# BTP_gateway_board.net
KiCad netlist of a schematic drawn in EAGLE
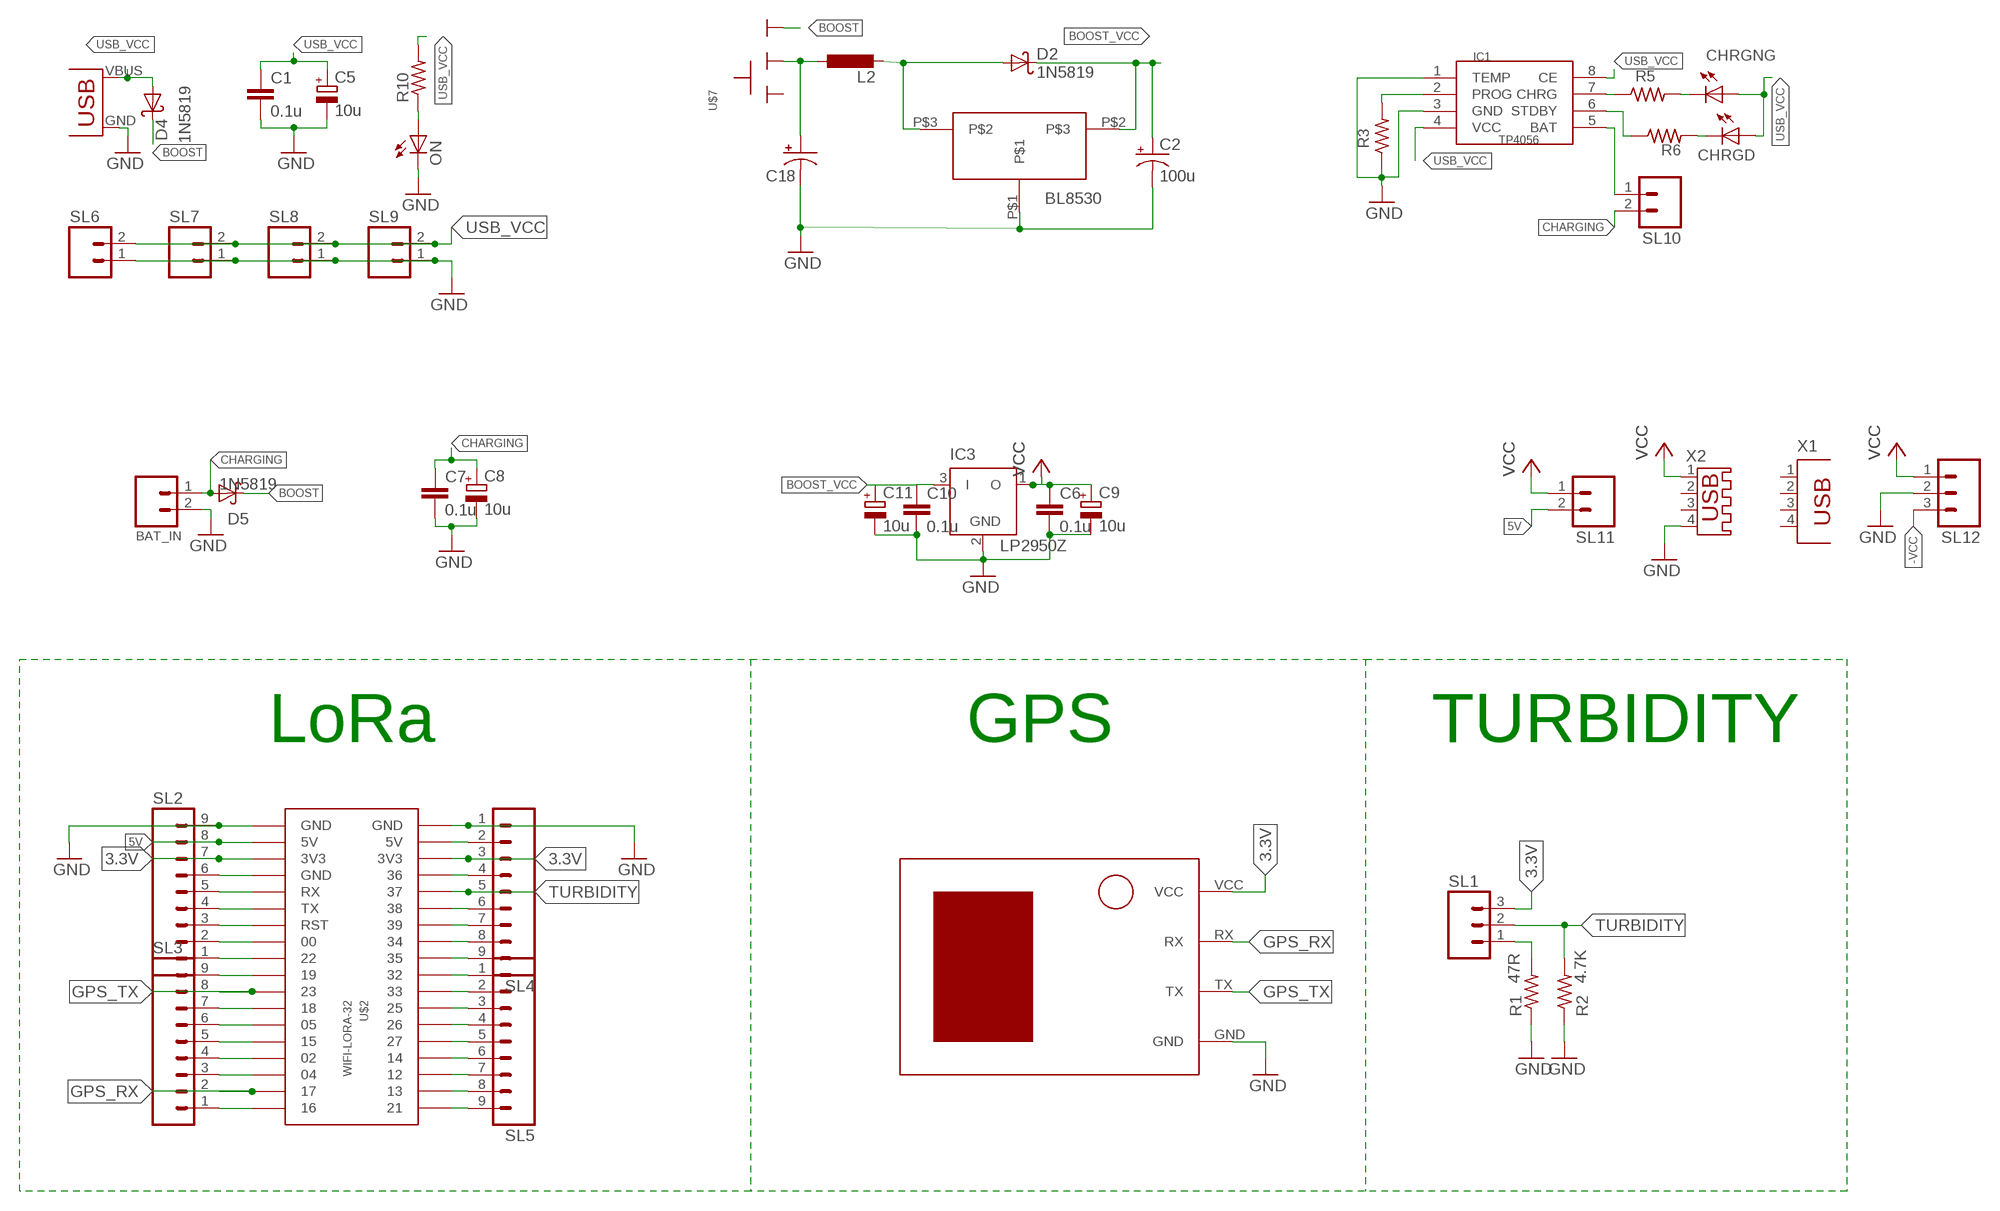
[diagram p0: schematic, sheet 1]

(export (version "E")
  (design (tool "Eeschema 10.0.6"))
  (components
    (comp (ref "BAT_IN")
      (value "M02")
      (footprint "eagle-import:02P")
      (fields (field (name "MF") "NEXPERIA") (field (name "MPN") "2N7002PW,115"))
      (libsource (lib "eagle-import") (part "M02"))
    )
    (comp (ref "BL1")
      (value "BL8530_5V")
      (footprint "eagle-import:BL8530_5V")
      (libsource (lib "eagle-import") (part "BL8530_5V"))
    )
    (comp (ref "C1")
      (value "0.1u")
      (footprint "eagle-import:C025-024X044")
      (libsource (lib "eagle-import") (part "C-EU025-024X044"))
    )
    (comp (ref "C2")
      (value "100u")
      (footprint "eagle-import:C_6032-28R")
      (libsource (lib "eagle-import") (part "CEDT_JANUARY_2015_v7_CAP_POL_10V"))
    )
    (comp (ref "C5")
      (value "10u")
      (footprint "eagle-import:E2,5-5")
      (libsource (lib "eagle-import") (part "CPOL-EUE2.5-5"))
    )
    (comp (ref "C6")
      (value "0.1u")
      (footprint "eagle-import:C025-024X044")
      (libsource (lib "eagle-import") (part "C-EU025-024X044"))
    )
    (comp (ref "C7")
      (value "0.1u")
      (footprint "eagle-import:C025-024X044")
      (libsource (lib "eagle-import") (part "C-EU025-024X044"))
    )
    (comp (ref "C8")
      (value "10u")
      (footprint "eagle-import:E2,5-5")
      (libsource (lib "eagle-import") (part "CPOL-EUE2.5-5"))
    )
    (comp (ref "C9")
      (value "10u")
      (footprint "eagle-import:E2,5-5")
      (libsource (lib "eagle-import") (part "CPOL-EUE2.5-5"))
    )
    (comp (ref "C10")
      (value "0.1u")
      (footprint "eagle-import:C025-024X044")
      (libsource (lib "eagle-import") (part "C-EU025-024X044"))
    )
    (comp (ref "C11")
      (value "10u")
      (footprint "eagle-import:E2,5-5")
      (libsource (lib "eagle-import") (part "CPOL-EUE2.5-5"))
    )
    (comp (ref "C18")
      (value "10u")
      (footprint "eagle-import:C_6032-28R")
      (libsource (lib "eagle-import") (part "CAP_POL_10V"))
    )
    (comp (ref "CHRGD")
      (value "LED3MM")
      (footprint "eagle-import:LED3MM")
      (libsource (lib "eagle-import") (part "LED3MM"))
    )
    (comp (ref "CHRGNG")
      (value "LED3MM")
      (footprint "eagle-import:LED3MM")
      (libsource (lib "eagle-import") (part "LED3MM"))
    )
    (comp (ref "D2")
      (value "1N5819")
      (footprint "eagle-import:DO41-10")
      (libsource (lib "eagle-import") (part "1N5819"))
    )
    (comp (ref "D4")
      (value "1N5819")
      (footprint "eagle-import:DO41-10")
      (libsource (lib "eagle-import") (part "1N5819"))
    )
    (comp (ref "D5")
      (value "1N5819")
      (footprint "eagle-import:DO41-10")
      (libsource (lib "eagle-import") (part "1N5819"))
    )
    (comp (ref "IC1")
      (value "TP4056")
      (footprint "eagle-import:SOP-8")
      (libsource (lib "eagle-import") (part "TP4056"))
    )
    (comp (ref "IC3")
      (value "LP2950Z")
      (footprint "eagle-import:TO92")
      (libsource (lib "eagle-import") (part "LP2950Z"))
    )
    (comp (ref "L2")
      (value "47uH")
      (footprint "eagle-import:L4532P")
      (libsource (lib "eagle-import") (part "L-EUL4532P"))
    )
    (comp (ref "ON")
      (value "LED3MM")
      (footprint "eagle-import:LED3MM")
      (libsource (lib "eagle-import") (part "CEDT_LED3MM"))
    )
    (comp (ref "R1")
      (value "47R")
      (footprint "eagle-import:0207_7")
      (libsource (lib "eagle-import") (part "CEDT_JANUARY_2015_v7_RESISTOR0207/7"))
    )
    (comp (ref "R2")
      (value "4.7K")
      (footprint "eagle-import:0207_7")
      (libsource (lib "eagle-import") (part "CEDT_JANUARY_2015_v7_RESISTOR0207/7"))
    )
    (comp (ref "R3")
      (value "10K")
      (footprint "eagle-import:R0805")
      (libsource (lib "eagle-import") (part "CEDT_JANUARY_2015_v5_RESISTOR0805"))
    )
    (comp (ref "R5")
      (value "470")
      (footprint "eagle-import:R0805")
      (libsource (lib "eagle-import") (part "CEDT_JANUARY_2015_v5_RESISTOR0805"))
    )
    (comp (ref "R6")
      (value "470")
      (footprint "eagle-import:R0805")
      (libsource (lib "eagle-import") (part "CEDT_JANUARY_2015_v5_RESISTOR0805"))
    )
    (comp (ref "R10")
      (value "RESISTOR0805")
      (footprint "eagle-import:R0805")
      (libsource (lib "eagle-import") (part "RESISTOR0805"))
    )
    (comp (ref "SL1")
      (value "M03")
      (footprint "eagle-import:03P")
      (libsource (lib "eagle-import") (part "M03"))
    )
    (comp (ref "SL2")
      (value "M09")
      (footprint "eagle-import:09P")
      (libsource (lib "eagle-import") (part "M09"))
    )
    (comp (ref "SL3")
      (value "M09")
      (footprint "eagle-import:09P")
      (libsource (lib "eagle-import") (part "M09"))
    )
    (comp (ref "SL4")
      (value "M09")
      (footprint "eagle-import:09P")
      (libsource (lib "eagle-import") (part "M09"))
    )
    (comp (ref "SL5")
      (value "M09")
      (footprint "eagle-import:09P")
      (libsource (lib "eagle-import") (part "M09"))
    )
    (comp (ref "SL6")
      (value "M02")
      (footprint "eagle-import:02P")
      (libsource (lib "eagle-import") (part "CEDT_JANUARY_2015_v7_M02"))
    )
    (comp (ref "SL7")
      (value "M02")
      (footprint "eagle-import:02P")
      (libsource (lib "eagle-import") (part "CEDT_JANUARY_2015_v7_M02"))
    )
    (comp (ref "SL8")
      (value "M02")
      (footprint "eagle-import:02P")
      (libsource (lib "eagle-import") (part "CEDT_JANUARY_2015_v7_M02"))
    )
    (comp (ref "SL9")
      (value "M02")
      (footprint "eagle-import:02P")
      (libsource (lib "eagle-import") (part "CEDT_JANUARY_2015_v7_M02"))
    )
    (comp (ref "SL10")
      (value "M02")
      (footprint "eagle-import:02P")
      (libsource (lib "eagle-import") (part "CEDT_JANUARY_2015_v7_M02"))
    )
    (comp (ref "SL11")
      (value "M02")
      (footprint "eagle-import:02P")
      (libsource (lib "eagle-import") (part "CEDT_JANUARY_2015_v7_M02"))
    )
    (comp (ref "SL12")
      (value "M03")
      (footprint "eagle-import:03P")
      (libsource (lib "eagle-import") (part "M03"))
    )
    (comp (ref "U$1")
      (value "U-BLOX-NEO6V2")
      (footprint "eagle-import:U-BLOX-NEO6V2")
      (libsource (lib "eagle-import") (part "U-BLOX-NEO6V2"))
    )
    (comp (ref "U$2")
      (value "WIFI-LORA-32")
      (footprint "eagle-import:2.54MM_2X18")
      (libsource (lib "eagle-import") (part "WIFI-LORA-32"))
    )
    (comp (ref "U$3")
      (value "USB(POWER)")
      (footprint "eagle-import:USB(POWER)")
      (libsource (lib "eagle-import") (part "USB(POWER)"))
    )
    (comp (ref "U$7")
      (value "SLIDESWITCH-SMALL")
      (footprint "eagle-import:SMALLSWITCH")
      (libsource (lib "eagle-import") (part "SLIDESWITCH-SMALL"))
    )
    (comp (ref "X1")
      (value "PN87520")
      (footprint "eagle-import:PN87520")
      (libsource (lib "eagle-import") (part "PN87520"))
    )
    (comp (ref "X2")
      (value "USB-A003")
      (footprint "eagle-import:USB-A003")
      (libsource (lib "eagle-import") (part "USB-A003"))
    )
  )
  (nets
    (net (code "1") (name "-VCC") (class "Default")
      (node (ref "SL12") (pin "3") (pinfunction "3_3") (pintype "passive"))
    )
    (net (code "2") (name "3.3V") (class "Default")
      (node (ref "SL1") (pin "3") (pinfunction "3_3") (pintype "passive"))
      (node (ref "SL2") (pin "7") (pinfunction "7_7") (pintype "passive"))
      (node (ref "SL4") (pin "3") (pinfunction "3_3") (pintype "passive"))
      (node (ref "U$1") (pin "VCC") (pinfunction "VCC_VCC") (pintype "bidirectional"))
      (node (ref "U$2") (pin "P$3") (pinfunction "3V3_P$3") (pintype "power_in"))
      (node (ref "U$2") (pin "P$34") (pinfunction "3V3_P$34") (pintype "power_in"))
    )
    (net (code "3") (name "5V") (class "Default")
      (node (ref "SL11") (pin "2") (pinfunction "2_2") (pintype "passive"))
      (node (ref "SL2") (pin "8") (pinfunction "8_8") (pintype "passive"))
      (node (ref "U$2") (pin "P$2") (pinfunction "5V_P$2") (pintype "power_in"))
    )
    (net (code "4") (name "BOOST") (class "Default")
      (node (ref "D4") (pin "C") (pinfunction "C_C") (pintype "passive"))
      (node (ref "D5") (pin "C") (pinfunction "C_C") (pintype "passive"))
      (node (ref "U$7") (pin "3") (pinfunction "3_3") (pintype "bidirectional"))
    )
    (net (code "5") (name "BOOST_VCC") (class "Default")
      (node (ref "BL1") (pin "P$2") (pinfunction "P$3_P$2") (pintype "bidirectional"))
      (node (ref "C10") (pin "1") (pinfunction "1_1") (pintype "passive"))
      (node (ref "C11") (pin "+") (pinfunction "+_+") (pintype "passive"))
      (node (ref "C2") (pin "+") (pinfunction "+_+") (pintype "passive"))
      (node (ref "D2") (pin "C") (pinfunction "C_C") (pintype "passive"))
      (node (ref "IC3") (pin "3") (pinfunction "I_3") (pintype "input"))
    )
    (net (code "6") (name "CHARGING") (class "Default")
      (node (ref "BAT_IN") (pin "1") (pinfunction "1_1") (pintype "passive"))
      (node (ref "C7") (pin "1") (pinfunction "1_1") (pintype "passive"))
      (node (ref "C8") (pin "+") (pinfunction "+_+") (pintype "passive"))
      (node (ref "D5") (pin "A") (pinfunction "A_A") (pintype "passive"))
      (node (ref "SL10") (pin "2") (pinfunction "2_2") (pintype "passive"))
    )
    (net (code "7") (name "GND") (class "Default")
      (node (ref "BAT_IN") (pin "2") (pinfunction "2_2") (pintype "passive"))
      (node (ref "BL1") (pin "P$1") (pinfunction "P$1_P$1") (pintype "bidirectional"))
      (node (ref "C1") (pin "2") (pinfunction "2_2") (pintype "passive"))
      (node (ref "C10") (pin "2") (pinfunction "2_2") (pintype "passive"))
      (node (ref "C11") (pin "-") (pinfunction "-_-") (pintype "passive"))
      (node (ref "C18") (pin "-") (pinfunction "-_-") (pintype "passive"))
      (node (ref "C2") (pin "-") (pinfunction "-_-") (pintype "passive"))
      (node (ref "C5") (pin "-") (pinfunction "-_-") (pintype "passive"))
      (node (ref "C6") (pin "2") (pinfunction "2_2") (pintype "passive"))
      (node (ref "C7") (pin "2") (pinfunction "2_2") (pintype "passive"))
      (node (ref "C8") (pin "-") (pinfunction "-_-") (pintype "passive"))
      (node (ref "C9") (pin "-") (pinfunction "-_-") (pintype "passive"))
      (node (ref "IC1") (pin "1") (pinfunction "TEMP_1") (pintype "bidirectional"))
      (node (ref "IC1") (pin "3") (pinfunction "GND_3") (pintype "bidirectional"))
      (node (ref "IC3") (pin "2") (pinfunction "GND_2") (pintype "power_in"))
      (node (ref "ON") (pin "K") (pinfunction "C_K") (pintype "passive"))
      (node (ref "R1") (pin "1") (pinfunction "1_1") (pintype "passive"))
      (node (ref "R2") (pin "1") (pinfunction "1_1") (pintype "passive"))
      (node (ref "R3") (pin "1") (pinfunction "1_1") (pintype "passive"))
      (node (ref "SL12") (pin "2") (pinfunction "2_2") (pintype "passive"))
      (node (ref "SL2") (pin "9") (pinfunction "9_9") (pintype "passive"))
      (node (ref "SL4") (pin "1") (pinfunction "1_1") (pintype "passive"))
      (node (ref "SL6") (pin "1") (pinfunction "1_1") (pintype "passive"))
      (node (ref "SL7") (pin "1") (pinfunction "1_1") (pintype "passive"))
      (node (ref "SL8") (pin "1") (pinfunction "1_1") (pintype "passive"))
      (node (ref "SL9") (pin "1") (pinfunction "1_1") (pintype "passive"))
      (node (ref "U$1") (pin "GND") (pinfunction "GND_GND") (pintype "bidirectional"))
      (node (ref "U$2") (pin "P$1") (pinfunction "GND_P$1") (pintype "power_in"))
      (node (ref "U$2") (pin "P$36") (pinfunction "GND_P$36") (pintype "power_in"))
      (node (ref "U$3") (pin "GND") (pinfunction "GND_GND") (pintype "power_in"))
      (node (ref "X2") (pin "4") (pinfunction "4_4") (pintype "passive"))
    )
    (net (code "8") (name "GPS_RX") (class "Default")
      (node (ref "SL3") (pin "2") (pinfunction "2_2") (pintype "passive"))
      (node (ref "U$1") (pin "RX") (pinfunction "RX_RX") (pintype "bidirectional"))
      (node (ref "U$2") (pin "P$17") (pinfunction "17_P$17") (pintype "bidirectional"))
    )
    (net (code "9") (name "GPS_TX") (class "Default")
      (node (ref "SL3") (pin "8") (pinfunction "8_8") (pintype "passive"))
      (node (ref "U$1") (pin "TX") (pinfunction "TX_TX") (pintype "bidirectional"))
      (node (ref "U$2") (pin "P$11") (pinfunction "23_P$11") (pintype "bidirectional"))
    )
    (net (code "10") (name "Net-(BL1-P$2)") (class "Default")
      (node (ref "BL1") (pin "P$3") (pinfunction "P$2_P$3") (pintype "bidirectional"))
      (node (ref "D2") (pin "A") (pinfunction "A_A") (pintype "passive"))
      (node (ref "L2") (pin "2") (pinfunction "2_2") (pintype "passive"))
    )
    (net (code "11") (name "Net-(C18-Pad+)") (class "Default")
      (node (ref "C18") (pin "+") (pinfunction "+_+") (pintype "passive"))
      (node (ref "L2") (pin "1") (pinfunction "1_1") (pintype "passive"))
      (node (ref "U$7") (pin "2") (pinfunction "2_2") (pintype "bidirectional"))
    )
    (net (code "12") (name "Net-(CHRGD-C)") (class "Default")
      (node (ref "CHRGD") (pin "K") (pinfunction "C_K") (pintype "passive"))
      (node (ref "R6") (pin "2") (pinfunction "2_2") (pintype "passive"))
    )
    (net (code "13") (name "Net-(CHRGNG-C)") (class "Default")
      (node (ref "CHRGNG") (pin "K") (pinfunction "C_K") (pintype "passive"))
      (node (ref "R5") (pin "2") (pinfunction "2_2") (pintype "passive"))
    )
    (net (code "14") (name "Net-(IC1-BAT)") (class "Default")
      (node (ref "IC1") (pin "5") (pinfunction "BAT_5") (pintype "bidirectional"))
      (node (ref "SL10") (pin "1") (pinfunction "1_1") (pintype "passive"))
    )
    (net (code "15") (name "Net-(IC1-CHRG)") (class "Default")
      (node (ref "IC1") (pin "7") (pinfunction "CHRG_7") (pintype "bidirectional"))
      (node (ref "R5") (pin "1") (pinfunction "1_1") (pintype "passive"))
    )
    (net (code "16") (name "Net-(IC1-PROG)") (class "Default")
      (node (ref "IC1") (pin "2") (pinfunction "PROG_2") (pintype "bidirectional"))
      (node (ref "R3") (pin "2") (pinfunction "2_2") (pintype "passive"))
    )
    (net (code "17") (name "Net-(IC1-STDBY)") (class "Default")
      (node (ref "IC1") (pin "6") (pinfunction "STDBY_6") (pintype "bidirectional"))
      (node (ref "R6") (pin "1") (pinfunction "1_1") (pintype "passive"))
    )
    (net (code "18") (name "Net-(ON-PadA)") (class "Default")
      (node (ref "ON") (pin "A") (pinfunction "A_A") (pintype "passive"))
      (node (ref "R10") (pin "1") (pinfunction "1_1") (pintype "passive"))
    )
    (net (code "19") (name "Net-(R1-Pad2)") (class "Default")
      (node (ref "R1") (pin "2") (pinfunction "2_2") (pintype "passive"))
      (node (ref "SL1") (pin "1") (pinfunction "1_1") (pintype "passive"))
    )
    (net (code "20") (name "Net-(SL2-Pad6)") (class "Default")
      (node (ref "SL2") (pin "6") (pinfunction "6_6") (pintype "passive"))
      (node (ref "U$2") (pin "P$4") (pinfunction "GND_P$4") (pintype "bidirectional"))
    )
    (net (code "21") (name "Net-(SL4-Pad2)") (class "Default")
      (node (ref "SL4") (pin "2") (pinfunction "2_2") (pintype "passive"))
      (node (ref "U$2") (pin "P$35") (pinfunction "5V_P$35") (pintype "power_in"))
    )
    (net (code "22") (name "Net-(U$2-00)") (class "Default")
      (node (ref "SL2") (pin "2") (pinfunction "2_2") (pintype "passive"))
      (node (ref "U$2") (pin "P$8") (pinfunction "00_P$8") (pintype "bidirectional"))
    )
    (net (code "23") (name "Net-(U$2-02)") (class "Default")
      (node (ref "SL3") (pin "4") (pinfunction "4_4") (pintype "passive"))
      (node (ref "U$2") (pin "P$15") (pinfunction "02_P$15") (pintype "bidirectional"))
    )
    (net (code "24") (name "Net-(U$2-04)") (class "Default")
      (node (ref "SL3") (pin "3") (pinfunction "3_3") (pintype "passive"))
      (node (ref "U$2") (pin "P$16") (pinfunction "04_P$16") (pintype "bidirectional"))
    )
    (net (code "25") (name "Net-(U$2-05)") (class "Default")
      (node (ref "SL3") (pin "6") (pinfunction "6_6") (pintype "passive"))
      (node (ref "U$2") (pin "P$13") (pinfunction "05_P$13") (pintype "bidirectional"))
    )
    (net (code "26") (name "Net-(U$2-12)") (class "Default")
      (node (ref "SL5") (pin "7") (pinfunction "7_7") (pintype "passive"))
      (node (ref "U$2") (pin "P$21") (pinfunction "12_P$21") (pintype "bidirectional"))
    )
    (net (code "27") (name "Net-(U$2-13)") (class "Default")
      (node (ref "SL5") (pin "8") (pinfunction "8_8") (pintype "passive"))
      (node (ref "U$2") (pin "P$20") (pinfunction "13_P$20") (pintype "bidirectional"))
    )
    (net (code "28") (name "Net-(U$2-14)") (class "Default")
      (node (ref "SL5") (pin "6") (pinfunction "6_6") (pintype "passive"))
      (node (ref "U$2") (pin "P$22") (pinfunction "14_P$22") (pintype "bidirectional"))
    )
    (net (code "29") (name "Net-(U$2-15)") (class "Default")
      (node (ref "SL3") (pin "5") (pinfunction "5_5") (pintype "passive"))
      (node (ref "U$2") (pin "P$14") (pinfunction "15_P$14") (pintype "bidirectional"))
    )
    (net (code "30") (name "Net-(U$2-16)") (class "Default")
      (node (ref "SL3") (pin "1") (pinfunction "1_1") (pintype "passive"))
      (node (ref "U$2") (pin "P$18") (pinfunction "16_P$18") (pintype "bidirectional"))
    )
    (net (code "31") (name "Net-(U$2-18)") (class "Default")
      (node (ref "SL3") (pin "7") (pinfunction "7_7") (pintype "passive"))
      (node (ref "U$2") (pin "P$12") (pinfunction "18_P$12") (pintype "bidirectional"))
    )
    (net (code "32") (name "Net-(U$2-19)") (class "Default")
      (node (ref "SL3") (pin "9") (pinfunction "9_9") (pintype "passive"))
      (node (ref "U$2") (pin "P$10") (pinfunction "19_P$10") (pintype "bidirectional"))
    )
    (net (code "33") (name "Net-(U$2-21)") (class "Default")
      (node (ref "SL5") (pin "9") (pinfunction "9_9") (pintype "passive"))
      (node (ref "U$2") (pin "P$19") (pinfunction "21_P$19") (pintype "bidirectional"))
    )
    (net (code "34") (name "Net-(U$2-22)") (class "Default")
      (node (ref "SL2") (pin "1") (pinfunction "1_1") (pintype "passive"))
      (node (ref "U$2") (pin "P$9") (pinfunction "22_P$9") (pintype "bidirectional"))
    )
    (net (code "35") (name "Net-(U$2-25)") (class "Default")
      (node (ref "SL5") (pin "3") (pinfunction "3_3") (pintype "passive"))
      (node (ref "U$2") (pin "P$25") (pinfunction "25_P$25") (pintype "bidirectional"))
    )
    (net (code "36") (name "Net-(U$2-26)") (class "Default")
      (node (ref "SL5") (pin "4") (pinfunction "4_4") (pintype "passive"))
      (node (ref "U$2") (pin "P$24") (pinfunction "26_P$24") (pintype "bidirectional"))
    )
    (net (code "37") (name "Net-(U$2-27)") (class "Default")
      (node (ref "SL5") (pin "5") (pinfunction "5_5") (pintype "passive"))
      (node (ref "U$2") (pin "P$23") (pinfunction "27_P$23") (pintype "bidirectional"))
    )
    (net (code "38") (name "Net-(U$2-32)") (class "Default")
      (node (ref "SL5") (pin "1") (pinfunction "1_1") (pintype "passive"))
      (node (ref "U$2") (pin "P$27") (pinfunction "32_P$27") (pintype "bidirectional"))
    )
    (net (code "39") (name "Net-(U$2-33)") (class "Default")
      (node (ref "SL5") (pin "2") (pinfunction "2_2") (pintype "passive"))
      (node (ref "U$2") (pin "P$26") (pinfunction "33_P$26") (pintype "bidirectional"))
    )
    (net (code "40") (name "Net-(U$2-34)") (class "Default")
      (node (ref "SL4") (pin "8") (pinfunction "8_8") (pintype "passive"))
      (node (ref "U$2") (pin "P$29") (pinfunction "34_P$29") (pintype "bidirectional"))
    )
    (net (code "41") (name "Net-(U$2-35)") (class "Default")
      (node (ref "SL4") (pin "9") (pinfunction "9_9") (pintype "passive"))
      (node (ref "U$2") (pin "P$28") (pinfunction "35_P$28") (pintype "bidirectional"))
    )
    (net (code "42") (name "Net-(U$2-36)") (class "Default")
      (node (ref "SL4") (pin "4") (pinfunction "4_4") (pintype "passive"))
      (node (ref "U$2") (pin "P$33") (pinfunction "36_P$33") (pintype "bidirectional"))
    )
    (net (code "43") (name "Net-(U$2-38)") (class "Default")
      (node (ref "SL4") (pin "6") (pinfunction "6_6") (pintype "passive"))
      (node (ref "U$2") (pin "P$31") (pinfunction "38_P$31") (pintype "bidirectional"))
    )
    (net (code "44") (name "Net-(U$2-39)") (class "Default")
      (node (ref "SL4") (pin "7") (pinfunction "7_7") (pintype "passive"))
      (node (ref "U$2") (pin "P$30") (pinfunction "39_P$30") (pintype "bidirectional"))
    )
    (net (code "45") (name "Net-(U$2-RST)") (class "Default")
      (node (ref "SL2") (pin "3") (pinfunction "3_3") (pintype "passive"))
      (node (ref "U$2") (pin "P$7") (pinfunction "RST_P$7") (pintype "bidirectional"))
    )
    (net (code "46") (name "Net-(U$2-RX)") (class "Default")
      (node (ref "SL2") (pin "5") (pinfunction "5_5") (pintype "passive"))
      (node (ref "U$2") (pin "P$5") (pinfunction "RX_P$5") (pintype "bidirectional"))
    )
    (net (code "47") (name "Net-(U$2-TX)") (class "Default")
      (node (ref "SL2") (pin "4") (pinfunction "4_4") (pintype "passive"))
      (node (ref "U$2") (pin "P$6") (pinfunction "TX_P$6") (pintype "bidirectional"))
    )
    (net (code "48") (name "TURBIDITY") (class "Default")
      (node (ref "R2") (pin "2") (pinfunction "2_2") (pintype "passive"))
      (node (ref "SL1") (pin "2") (pinfunction "2_2") (pintype "passive"))
      (node (ref "SL4") (pin "5") (pinfunction "5_5") (pintype "passive"))
      (node (ref "U$2") (pin "P$32") (pinfunction "37_P$32") (pintype "bidirectional"))
    )
    (net (code "49") (name "USB_VCC") (class "Default")
      (node (ref "C1") (pin "1") (pinfunction "1_1") (pintype "passive"))
      (node (ref "C5") (pin "+") (pinfunction "+_+") (pintype "passive"))
      (node (ref "CHRGD") (pin "A") (pinfunction "A_A") (pintype "passive"))
      (node (ref "CHRGNG") (pin "A") (pinfunction "A_A") (pintype "passive"))
      (node (ref "D4") (pin "A") (pinfunction "A_A") (pintype "passive"))
      (node (ref "IC1") (pin "4") (pinfunction "VCC_4") (pintype "bidirectional"))
      (node (ref "IC1") (pin "8") (pinfunction "CE_8") (pintype "bidirectional"))
      (node (ref "R10") (pin "2") (pinfunction "2_2") (pintype "passive"))
      (node (ref "SL6") (pin "2") (pinfunction "2_2") (pintype "passive"))
      (node (ref "SL7") (pin "2") (pinfunction "2_2") (pintype "passive"))
      (node (ref "SL8") (pin "2") (pinfunction "2_2") (pintype "passive"))
      (node (ref "SL9") (pin "2") (pinfunction "2_2") (pintype "passive"))
      (node (ref "U$3") (pin "VBUS") (pinfunction "VCC_VBUS") (pintype "power_in"))
    )
    (net (code "50") (name "VCC") (class "Default")
      (node (ref "C6") (pin "1") (pinfunction "1_1") (pintype "passive"))
      (node (ref "C9") (pin "+") (pinfunction "+_+") (pintype "passive"))
      (node (ref "IC3") (pin "1") (pinfunction "O_1") (pintype "input"))
      (node (ref "SL11") (pin "1") (pinfunction "1_1") (pintype "passive"))
      (node (ref "SL12") (pin "1") (pinfunction "1_1") (pintype "passive"))
      (node (ref "X2") (pin "1") (pinfunction "1_1") (pintype "passive"))
    )
    (net (code "51") (name "unconnected-(U$7-Pad1)") (class "Default")
      (node (ref "U$7") (pin "1") (pinfunction "1_1") (pintype "bidirectional"))
    )
    (net (code "52") (name "unconnected-(X1-Pad1)") (class "Default")
      (node (ref "X1") (pin "1") (pinfunction "1_1") (pintype "passive"))
    )
    (net (code "53") (name "unconnected-(X1-Pad2)") (class "Default")
      (node (ref "X1") (pin "2") (pinfunction "2_2") (pintype "passive"))
    )
    (net (code "54") (name "unconnected-(X1-Pad3)") (class "Default")
      (node (ref "X1") (pin "3") (pinfunction "3_3") (pintype "passive"))
    )
    (net (code "55") (name "unconnected-(X1-Pad4)") (class "Default")
      (node (ref "X1") (pin "4") (pinfunction "4_4") (pintype "passive"))
    )
    (net (code "56") (name "unconnected-(X2-Pad2)") (class "Default")
      (node (ref "X2") (pin "2") (pinfunction "2_2") (pintype "passive"))
    )
    (net (code "57") (name "unconnected-(X2-Pad3)") (class "Default")
      (node (ref "X2") (pin "3") (pinfunction "3_3") (pintype "passive"))
    )
  )
)
